# MEMS_LIP.net
KiCad netlist of a schematic drawn in Altium Designer
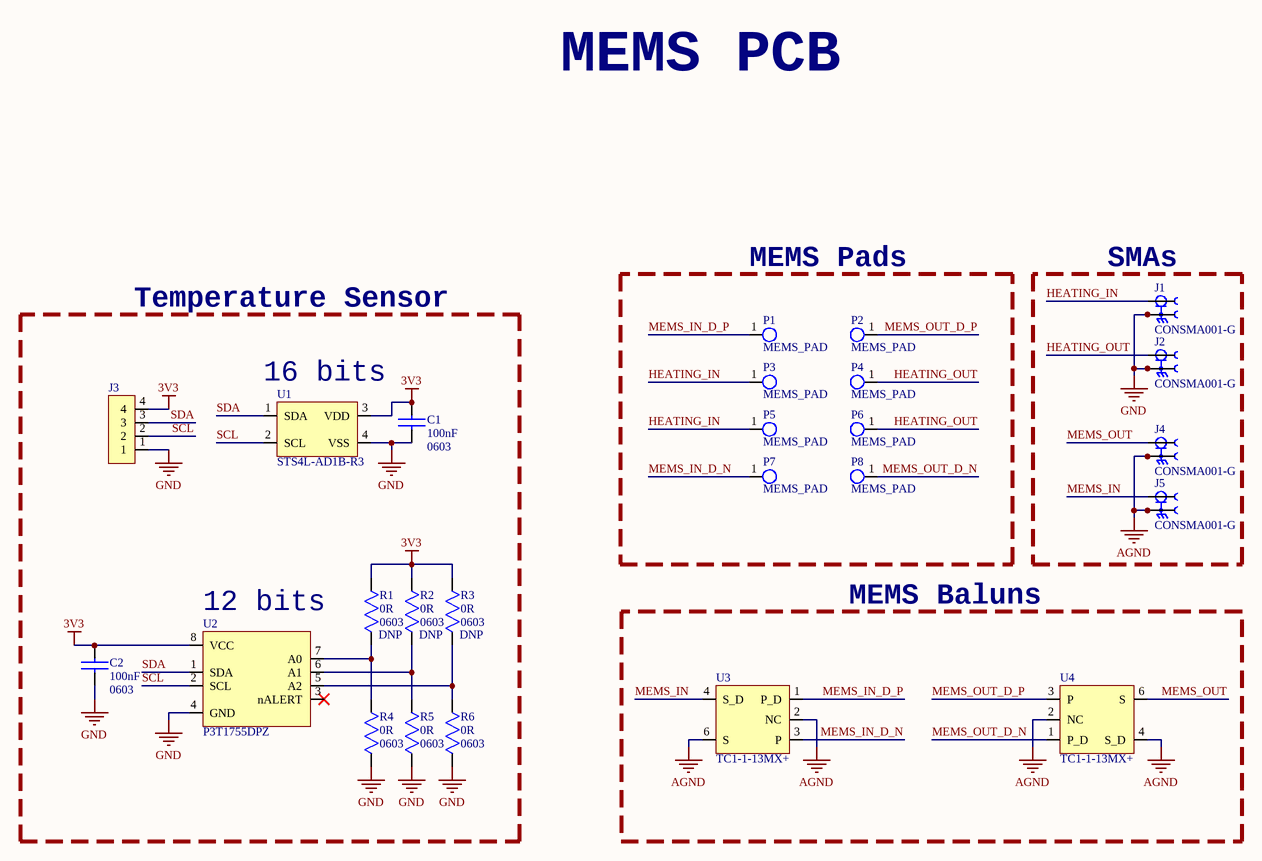
[diagram p0: MEMS_LIP.SchDoc]

(export (version "E")
  (design (tool "Eeschema 10.0.6"))
  (components
    (comp (ref "C1")
      (value "100nF")
      (footprint "C0603")
      (description "CAP CER 100NF 100V X8L 0603")
      (fields
        (field (name "MANUFACTURER") "Samsung")
        (field (name "MANUFACTURER PART NUMBER") "CL10E104KC8VPNC")
        (field (name "CASE") "0603")
      )
      (libsource (lib "MEMS_LIB") (part "CL10E104KC8VPNC"))
    )
    (comp (ref "C2")
      (value "100nF")
      (footprint "C0603")
      (description "CAP CER 100NF 100V X8L 0603")
      (fields
        (field (name "MANUFACTURER") "Samsung")
        (field (name "MANUFACTURER PART NUMBER") "CL10E104KC8VPNC")
        (field (name "CASE") "0603")
      )
      (libsource (lib "MEMS_LIB") (part "CL10E104KC8VPNC"))
    )
    (comp (ref "J1")
      (value "CONSMA001-G")
      (footprint "CONSMA001-G")
      (description "CONN SMA RCPT STR 50 OHM PCB")
      (libsource (lib "MEMS_LIB") (part "CONSMA001-G"))
    )
    (comp (ref "J2")
      (value "CONSMA001-G")
      (footprint "CONSMA001-G")
      (description "CONN SMA RCPT STR 50 OHM PCB")
      (libsource (lib "MEMS_LIB") (part "CONSMA001-G"))
    )
    (comp (ref "J3")
      (value "61300411121")
      (footprint "WURTH_61300411121")
      (description "CONN HEADER VERT 4POS 2.54MM")
      (fields (field (name "MF") "WÃ¼rth Elektronik"))
      (libsource (lib "MEMS_LIB") (part "61300411121"))
    )
    (comp (ref "J4")
      (value "CONSMA001-G")
      (footprint "CONSMA001-G")
      (description "CONN SMA RCPT STR 50 OHM PCB")
      (libsource (lib "MEMS_LIB") (part "CONSMA001-G"))
    )
    (comp (ref "J5")
      (value "CONSMA001-G")
      (footprint "CONSMA001-G")
      (description "CONN SMA RCPT STR 50 OHM PCB")
      (libsource (lib "MEMS_LIB") (part "CONSMA001-G"))
    )
    (comp (ref "P1")
      (value "MEMS_PAD")
      (footprint "MEMS_PAD")
      (description "PAD MEMS connection")
      (libsource (lib "MEMS_LIB") (part "MEMS_PAD"))
    )
    (comp (ref "P2")
      (value "MEMS_PAD")
      (footprint "MEMS_PAD")
      (description "PAD MEMS connection")
      (libsource (lib "MEMS_LIB") (part "MEMS_PAD"))
    )
    (comp (ref "P3")
      (value "MEMS_PAD")
      (footprint "MEMS_PAD")
      (description "PAD MEMS connection")
      (libsource (lib "MEMS_LIB") (part "MEMS_PAD"))
    )
    (comp (ref "P4")
      (value "MEMS_PAD")
      (footprint "MEMS_PAD")
      (description "PAD MEMS connection")
      (libsource (lib "MEMS_LIB") (part "MEMS_PAD"))
    )
    (comp (ref "P5")
      (value "MEMS_PAD")
      (footprint "MEMS_PAD")
      (description "PAD MEMS connection")
      (libsource (lib "MEMS_LIB") (part "MEMS_PAD"))
    )
    (comp (ref "P6")
      (value "MEMS_PAD")
      (footprint "MEMS_PAD")
      (description "PAD MEMS connection")
      (libsource (lib "MEMS_LIB") (part "MEMS_PAD"))
    )
    (comp (ref "P7")
      (value "MEMS_PAD")
      (footprint "MEMS_PAD")
      (description "PAD MEMS connection")
      (libsource (lib "MEMS_LIB") (part "MEMS_PAD"))
    )
    (comp (ref "P8")
      (value "MEMS_PAD")
      (footprint "MEMS_PAD")
      (description "PAD MEMS connection")
      (libsource (lib "MEMS_LIB") (part "MEMS_PAD"))
    )
    (comp (ref "R1")
      (value "0R")
      (footprint "R0603")
      (description "RES 0 OHM JUMPER 1/10W 0603")
      (fields
        (field (name "MF") "Stackpole Electronics")
        (field (name "MP") "RMCF0603ZT0R00")
        (field (name "PACKAGE") "0603")
      )
      (libsource (lib "MEMS_LIB") (part "RMCF0603ZT0R00"))
    )
    (comp (ref "R2")
      (value "0R")
      (footprint "R0603")
      (description "RES 0 OHM JUMPER 1/10W 0603")
      (fields
        (field (name "MF") "Stackpole Electronics")
        (field (name "MP") "RMCF0603ZT0R00")
        (field (name "PACKAGE") "0603")
      )
      (libsource (lib "MEMS_LIB") (part "RMCF0603ZT0R00"))
    )
    (comp (ref "R3")
      (value "0R")
      (footprint "R0603")
      (description "RES 0 OHM JUMPER 1/10W 0603")
      (fields
        (field (name "MF") "Stackpole Electronics")
        (field (name "MP") "RMCF0603ZT0R00")
        (field (name "PACKAGE") "0603")
      )
      (libsource (lib "MEMS_LIB") (part "RMCF0603ZT0R00"))
    )
    (comp (ref "R4")
      (value "0R")
      (footprint "R0603")
      (description "RES 0 OHM JUMPER 1/10W 0603")
      (fields
        (field (name "MF") "Stackpole Electronics")
        (field (name "MP") "RMCF0603ZT0R00")
        (field (name "PACKAGE") "0603")
      )
      (libsource (lib "MEMS_LIB") (part "RMCF0603ZT0R00"))
    )
    (comp (ref "R5")
      (value "0R")
      (footprint "R0603")
      (description "RES 0 OHM JUMPER 1/10W 0603")
      (fields
        (field (name "MF") "Stackpole Electronics")
        (field (name "MP") "RMCF0603ZT0R00")
        (field (name "PACKAGE") "0603")
      )
      (libsource (lib "MEMS_LIB") (part "RMCF0603ZT0R00"))
    )
    (comp (ref "R6")
      (value "0R")
      (footprint "R0603")
      (description "RES 0 OHM JUMPER 1/10W 0603")
      (fields
        (field (name "MF") "Stackpole Electronics")
        (field (name "MP") "RMCF0603ZT0R00")
        (field (name "PACKAGE") "0603")
      )
      (libsource (lib "MEMS_LIB") (part "RMCF0603ZT0R00"))
    )
    (comp (ref "U1")
      (value "STS4L-AD1B-R3")
      (footprint "STS4L-AD1B-R3")
      (description "IC - TEMPERATURE SENSOR 4-DFN")
      (libsource (lib "MEMS_LIB") (part "STS4L-AD1B-R3"))
    )
    (comp (ref "U2")
      (value "P3T1755DPZ")
      (footprint "TSSOP8_P3T1755DPZ_NXP")
      (description "SENSOR DGTL -40C ~ 125C 8-TSSOP")
      (libsource (lib "MEMS_LIB") (part "P3T1755DPZ"))
    )
    (comp (ref "U3")
      (value "TC1-1-13MX+")
      (footprint "TC1-1-13MX+")
      (description "1:1 CORE & WIRE TRANSFORMER, 4.5")
      (libsource (lib "MEMS_LIB") (part "TC1-1-13MX+"))
    )
    (comp (ref "U4")
      (value "TC1-1-13MX+")
      (footprint "TC1-1-13MX+")
      (description "1:1 CORE & WIRE TRANSFORMER, 4.5")
      (libsource (lib "") (part "TC1-1-13MX+_1"))
    )
  )
  (nets
    (net (code "1") (name "/HEATING_IN") (class "Default")
      (node (ref "J1") (pin "1") (pinfunction "1_1") (pintype "passive"))
      (node (ref "P3") (pin "1") (pinfunction "1_1") (pintype "passive"))
      (node (ref "P5") (pin "1") (pinfunction "1_1") (pintype "passive"))
    )
    (net (code "2") (name "/HEATING_OUT") (class "Default")
      (node (ref "J2") (pin "1") (pinfunction "1_1") (pintype "passive"))
      (node (ref "P4") (pin "1") (pinfunction "1_1") (pintype "passive"))
      (node (ref "P6") (pin "1") (pinfunction "1_1") (pintype "passive"))
    )
    (net (code "3") (name "/MEMS_IN") (class "Default")
      (node (ref "J5") (pin "1") (pinfunction "1_1") (pintype "passive"))
      (node (ref "U3") (pin "4") (pinfunction "S_D_4") (pintype "passive"))
    )
    (net (code "4") (name "/MEMS_IN_D_N") (class "Default")
      (node (ref "P7") (pin "1") (pinfunction "1_1") (pintype "passive"))
      (node (ref "U3") (pin "3") (pinfunction "P_3") (pintype "passive"))
    )
    (net (code "5") (name "/MEMS_IN_D_P") (class "Default")
      (node (ref "P1") (pin "1") (pinfunction "1_1") (pintype "passive"))
      (node (ref "U3") (pin "1") (pinfunction "P_D_1") (pintype "passive"))
    )
    (net (code "6") (name "/MEMS_OUT") (class "Default")
      (node (ref "J4") (pin "1") (pinfunction "1_1") (pintype "passive"))
      (node (ref "U4") (pin "6") (pinfunction "S_6") (pintype "passive"))
    )
    (net (code "7") (name "/MEMS_OUT_D_N") (class "Default")
      (node (ref "P8") (pin "1") (pinfunction "1_1") (pintype "passive"))
      (node (ref "U4") (pin "1") (pinfunction "P_D_1") (pintype "passive"))
    )
    (net (code "8") (name "/MEMS_OUT_D_P") (class "Default")
      (node (ref "P2") (pin "1") (pinfunction "1_1") (pintype "passive"))
      (node (ref "U4") (pin "3") (pinfunction "P_3") (pintype "passive"))
    )
    (net (code "9") (name "/SCL") (class "Default")
      (node (ref "J3") (pin "2") (pinfunction "2_2") (pintype "passive"))
      (node (ref "U1") (pin "2") (pinfunction "SCL_2") (pintype "passive"))
      (node (ref "U2") (pin "2") (pinfunction "SCL_2") (pintype "passive"))
    )
    (net (code "10") (name "/SDA") (class "Default")
      (node (ref "J3") (pin "3") (pinfunction "3_3") (pintype "passive"))
      (node (ref "U1") (pin "1") (pinfunction "SDA_1") (pintype "passive"))
      (node (ref "U2") (pin "1") (pinfunction "SDA_1") (pintype "passive"))
    )
    (net (code "11") (name "3V3") (class "Default")
      (node (ref "C1") (pin "1") (pinfunction "1_1") (pintype "passive"))
      (node (ref "C2") (pin "1") (pinfunction "1_1") (pintype "passive"))
      (node (ref "J3") (pin "4") (pinfunction "4_4") (pintype "passive"))
      (node (ref "R1") (pin "2") (pinfunction "2_2") (pintype "passive"))
      (node (ref "R2") (pin "2") (pinfunction "2_2") (pintype "passive"))
      (node (ref "R3") (pin "2") (pinfunction "2_2") (pintype "passive"))
      (node (ref "U1") (pin "3") (pinfunction "VDD_3") (pintype "passive"))
      (node (ref "U2") (pin "8") (pinfunction "VCC_8") (pintype "power_in"))
    )
    (net (code "12") (name "AGND") (class "Default")
      (node (ref "J4") (pin "S1") (pinfunction "2_S1") (pintype "passive"))
      (node (ref "J4") (pin "S2") (pinfunction "2_S2") (pintype "passive"))
      (node (ref "J4") (pin "S3") (pinfunction "2_S3") (pintype "passive"))
      (node (ref "J4") (pin "S4") (pinfunction "2_S4") (pintype "passive"))
      (node (ref "J5") (pin "S1") (pinfunction "2_S1") (pintype "passive"))
      (node (ref "J5") (pin "S2") (pinfunction "2_S2") (pintype "passive"))
      (node (ref "J5") (pin "S3") (pinfunction "2_S3") (pintype "passive"))
      (node (ref "J5") (pin "S4") (pinfunction "2_S4") (pintype "passive"))
      (node (ref "U3") (pin "2") (pinfunction "NC_2") (pintype "passive"))
      (node (ref "U3") (pin "6") (pinfunction "S_6") (pintype "passive"))
      (node (ref "U4") (pin "2") (pinfunction "NC_2") (pintype "passive"))
      (node (ref "U4") (pin "4") (pinfunction "S_D_4") (pintype "passive"))
    )
    (net (code "13") (name "GND") (class "Default")
      (node (ref "C1") (pin "2") (pinfunction "2_2") (pintype "passive"))
      (node (ref "C2") (pin "2") (pinfunction "2_2") (pintype "passive"))
      (node (ref "J1") (pin "S1") (pinfunction "2_S1") (pintype "passive"))
      (node (ref "J1") (pin "S2") (pinfunction "2_S2") (pintype "passive"))
      (node (ref "J1") (pin "S3") (pinfunction "2_S3") (pintype "passive"))
      (node (ref "J1") (pin "S4") (pinfunction "2_S4") (pintype "passive"))
      (node (ref "J2") (pin "S1") (pinfunction "2_S1") (pintype "passive"))
      (node (ref "J2") (pin "S2") (pinfunction "2_S2") (pintype "passive"))
      (node (ref "J2") (pin "S3") (pinfunction "2_S3") (pintype "passive"))
      (node (ref "J2") (pin "S4") (pinfunction "2_S4") (pintype "passive"))
      (node (ref "J3") (pin "1") (pinfunction "1_1") (pintype "passive"))
      (node (ref "R4") (pin "1") (pinfunction "1_1") (pintype "passive"))
      (node (ref "R5") (pin "1") (pinfunction "1_1") (pintype "passive"))
      (node (ref "R6") (pin "1") (pinfunction "1_1") (pintype "passive"))
      (node (ref "U1") (pin "4") (pinfunction "VSS_4") (pintype "passive"))
      (node (ref "U2") (pin "4") (pinfunction "GND_4") (pintype "power_in"))
    )
    (net (code "14") (name "Net-(U2-A0)") (class "Default")
      (node (ref "R1") (pin "1") (pinfunction "1_1") (pintype "passive"))
      (node (ref "R4") (pin "2") (pinfunction "2_2") (pintype "passive"))
      (node (ref "U2") (pin "7") (pinfunction "A0_7") (pintype "passive"))
    )
    (net (code "15") (name "Net-(U2-A1)") (class "Default")
      (node (ref "R2") (pin "1") (pinfunction "1_1") (pintype "passive"))
      (node (ref "R5") (pin "2") (pinfunction "2_2") (pintype "passive"))
      (node (ref "U2") (pin "6") (pinfunction "A1_6") (pintype "passive"))
    )
    (net (code "16") (name "Net-(U2-A2)") (class "Default")
      (node (ref "R3") (pin "1") (pinfunction "1_1") (pintype "passive"))
      (node (ref "R6") (pin "2") (pinfunction "2_2") (pintype "passive"))
      (node (ref "U2") (pin "5") (pinfunction "A2_5") (pintype "passive"))
    )
    (net (code "17") (name "unconnected-(U2-nALERT-Pad3)") (class "Default")
      (node (ref "U2") (pin "3") (pinfunction "nALERT_3") (pintype "passive+no_connect"))
    )
  )
)
